# CAN_Interface.net
KiCad netlist of a schematic drawn in Altium Designer
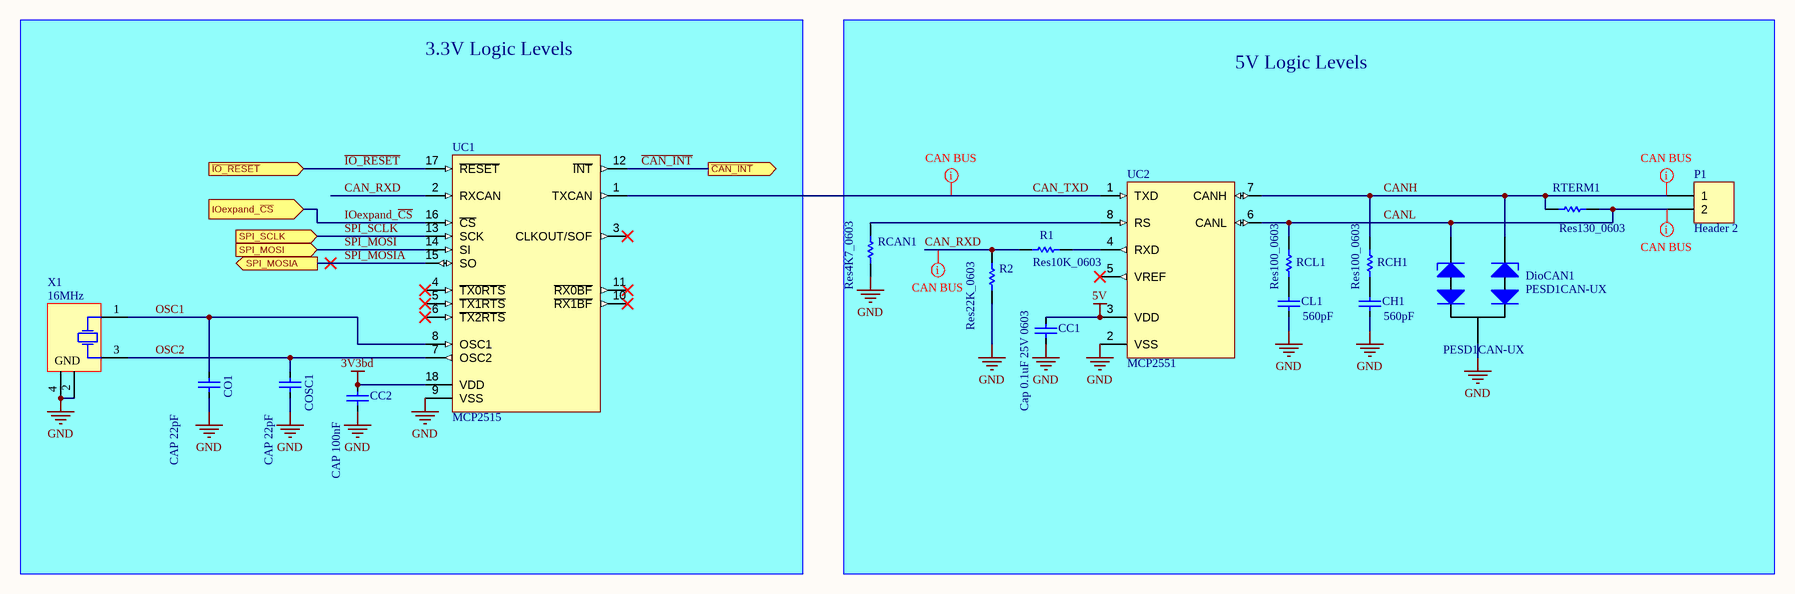
[diagram p0:  CAN_Interface.SchDoc]

(export (version "E")
  (design (tool "Eeschema 10.0.6"))
  (components
    (comp (ref "CC1")
      (value "Cap 0.1uF 25V 0603")
      (footprint "0603C_L")
      (description "Cap0.1uF_25V_0603")
      (libsource (lib "MHH -  Altium Advanced Course A365 01") (part "CMP-00001-1"))
    )
    (comp (ref "CC2")
      (value "CAP 100nF")
      (footprint "0603C_L")
      (fields
        (field (name "MANUFACTURER") "Yageo")
        (field (name "MANUFACTURER PART NUMBER") "CC0603ZRY5V9BB104")
      )
      (libsource (lib "MHH -  Altium Advanced Course A365 01") (part "CMP-00119-2"))
    )
    (comp (ref "CH1")
      (value "560pF")
      (footprint "0603C_L")
      (description "560pF 25V 0603")
      (libsource (lib "MHH -  Altium Advanced Course A365 01") (part "CAP Horizontal Pin50mil"))
    )
    (comp (ref "CL1")
      (value "560pF")
      (footprint "0603C_L")
      (description "560pF 25V 0603")
      (libsource (lib "MHH -  Altium Advanced Course A365 01") (part "CAP Horizontal Pin50mil"))
    )
    (comp (ref "CO1")
      (value "CAP 22pF")
      (footprint "0603C_L")
      (fields
        (field (name "TOLERANCE") "5%")
        (field (name "MANUFACTURER") "Murata")
        (field (name "MANUFACTURER PART NUMBER") "GRM1885C1H220JA01D")
      )
      (libsource (lib "MHH -  Altium Advanced Course A365 01") (part "CMP-00026-1"))
    )
    (comp (ref "COSC1")
      (value "CAP 22pF")
      (footprint "0603C_L")
      (fields
        (field (name "TOLERANCE") "5%")
        (field (name "MANUFACTURER") "Murata")
        (field (name "MANUFACTURER PART NUMBER") "GRM1885C1H220JA01D")
      )
      (libsource (lib "MHH -  Altium Advanced Course A365 01") (part "CMP-00026-1"))
    )
    (comp (ref "DioCAN1")
      (value "PESD1CAN-UX")
      (footprint "SOT323")
      (description "Trans Voltage Suppressor Diode, 150W, 24V V(RWM), Bidirectional, 2 Element, Silicon")
      (fields
        (field (name "MANUFACTURER") "Nexperia")
        (field (name "MANUFACTURER PART NUMBER") "PESD1CAN-UX")
        (field (name "SOURCE") "WCT.SchLib")
      )
      (libsource (lib "MHH -  Altium Advanced Course A365 01") (part "CMP-00244-2"))
    )
    (comp (ref "P1")
      (value "Header 2")
      (footprint "HDR1X2")
      (description "Header, 2-Pin")
      (fields (field (name "PUBLISHER") "Altium Limited") (field (name "SOURCE") "WCT.SchLib"))
      (libsource (lib "MHH -  Altium Advanced Course A365 01") (part "Header 2"))
    )
    (comp (ref "R1")
      (value "Res10K_0603")
      (footprint "0603_L")
      (fields
        (field (name "MANUFACTURER") "Panasonic")
        (field (name "MANUFACTURER PART NUMBER") "ERJ-3GEYJ102V")
        (field (name "TOLERANCE") "5%")
        (field (name "SOURCE") "WCT.SchLib")
      )
      (libsource (lib "MHH -  Altium Advanced Course A365 01") (part "CMP-00098-1"))
    )
    (comp (ref "R2")
      (value "Res22K_0603")
      (footprint "0603_L")
      (description "RES22K 0.5% 0603")
      (fields
        (field (name "MANUFACTURER") "Yageo")
        (field (name "MANUFACTURER PART NUMBER") "RT0603DRD0722KL")
        (field (name "SOURCE") "WCT.SchLib")
      )
      (libsource (lib "MHH -  Altium Advanced Course A365 01") (part "CMP-00098-1"))
    )
    (comp (ref "RCAN1")
      (value "Res4K7_0603")
      (footprint "0603_L")
      (fields
        (field (name "MANUFACTURER") "Yageo")
        (field (name "MANUFACTURER PART NUMBER") "RT0603DRD074K99L")
        (field (name "TOLERANCE") "0.5%")
        (field (name "SOURCE") "WCT.SchLib")
      )
      (libsource (lib "MHH -  Altium Advanced Course A365 01") (part "CMP-00016-1"))
    )
    (comp (ref "RCH1")
      (value "Res100_0603")
      (footprint "0603_L")
      (fields
        (field (name "MANUFACTURER") "Panasonic Electronic Components")
        (field (name "TOLERANCE") "5%")
        (field (name "SOURCE") "WCT.SchLib")
      )
      (libsource (lib "MHH -  Altium Advanced Course A365 01") (part "CMP-00096-1"))
    )
    (comp (ref "RCL1")
      (value "Res100_0603")
      (footprint "0603_L")
      (fields
        (field (name "MANUFACTURER") "Panasonic Electronic Components")
        (field (name "TOLERANCE") "5%")
        (field (name "SOURCE") "WCT.SchLib")
      )
      (libsource (lib "MHH -  Altium Advanced Course A365 01") (part "CMP-00096-1"))
    )
    (comp (ref "RTERM1")
      (value "Res130_0603")
      (footprint "0603_L")
      (fields
        (field (name "MANUFACTURER") "Panasonic Electronic Components")
        (field (name "TOLERANCE") "5%")
        (field (name "SOURCE") "WCT.SchLib")
      )
      (libsource (lib "MHH -  Altium Advanced Course A365 01") (part "CMP-00199-1"))
    )
    (comp (ref "UC1")
      (value "MCP2515")
      (footprint "SOIC-SO18_M")
      (description "Stand-Alone CAN Controller With SPI Interface, 18-Pin SOIC, Extended Temperature")
      (fields
        (field (name "MANUFACTURER") "Microchip")
        (field (name "MANUFACTURER PART NUMBER") "MCP2515-E/SO")
        (field (name "AVAILABLE PREVIEW IMAGES") "2D")
        (field (name "SOURCE") "WCT.SchLib")
      )
      (libsource (lib "MHH -  Altium Advanced Course A365 01") (part "MCP2515"))
    )
    (comp (ref "UC2")
      (value "MCP2551")
      (footprint "SOIC-SN8_N")
      (description "High-Speed CAN Transceiver, 8-Pin SOIC, Extended Temperature")
      (fields
        (field (name "MANUFACTURER") "Microchip")
        (field (name "MANUFACTURER PART NUMBER") "MCP2551-E/SN")
        (field (name "AVAILABLE PREVIEW IMAGES") "2D")
        (field (name "SOURCE") "WCT.SchLib")
      )
      (libsource (lib "MHH -  Altium Advanced Course A365 01") (part "MCP2551"))
    )
    (comp (ref "X1")
      (value "Crystal 4Pin")
      (footprint "FP-ABM8-MFG")
      (description "Crystal 16MHz ±20ppm 18pF SMD-4 3.2mm x 2.5mm CSTCE16M0V53-R0 ABM8-16.000MHZ-B2-T")
      (fields
        (field (name "TOLERANCE") "20ppm")
        (field (name "FREQUENCY") "16MHz")
        (field (name "MANUFACTURER") "Murata")
        (field (name "SOURCE") "WCT.SchLib")
      )
      (libsource (lib "MHH -  Altium Advanced Course A365 01") (part "Crystal 4Pin"))
    )
  )
  (nets
    (net (code "1") (name "/CANH") (class "Default")
      (node (ref "DioCAN1") (pin "1") (pinfunction "A_1") (pintype "passive"))
      (node (ref "P1") (pin "1") (pinfunction "1_1") (pintype "passive"))
      (node (ref "RCH1") (pin "2") (pinfunction "2_2") (pintype "passive"))
      (node (ref "RTERM1") (pin "2") (pinfunction "2_2") (pintype "passive"))
      (node (ref "UC2") (pin "7") (pinfunction "CANH_7") (pintype "bidirectional"))
    )
    (net (code "2") (name "/CANL") (class "Default")
      (node (ref "DioCAN1") (pin "2") (pinfunction "K_2") (pintype "passive"))
      (node (ref "P1") (pin "2") (pinfunction "2_2") (pintype "passive"))
      (node (ref "RCL1") (pin "2") (pinfunction "2_2") (pintype "passive"))
      (node (ref "RTERM1") (pin "1") (pinfunction "1_1") (pintype "passive"))
      (node (ref "UC2") (pin "6") (pinfunction "CANL_6") (pintype "bidirectional"))
    )
    (net (code "3") (name "/CAN_INT") (class "Default")
      (node (ref "UC1") (pin "12") (pinfunction "~{INT}_12") (pintype "output"))
    )
    (net (code "4") (name "/CAN_RXD") (class "Default")
      (node (ref "R1") (pin "2") (pinfunction "2_2") (pintype "passive"))
      (node (ref "R2") (pin "2") (pinfunction "2_2") (pintype "passive"))
      (node (ref "UC1") (pin "2") (pinfunction "RXCAN_2") (pintype "input"))
    )
    (net (code "5") (name "/CAN_TXD") (class "Default")
      (node (ref "UC1") (pin "1") (pinfunction "TXCAN_1") (pintype "output"))
      (node (ref "UC2") (pin "1") (pinfunction "TXD_1") (pintype "input"))
    )
    (net (code "6") (name "/IO_RESET") (class "Default")
      (node (ref "UC1") (pin "17") (pinfunction "~{RESET}_17") (pintype "input"))
    )
    (net (code "7") (name "/IOexpand_~{CS}") (class "Default")
      (node (ref "UC1") (pin "16") (pinfunction "~{CS}_16") (pintype "input"))
    )
    (net (code "8") (name "/OSC1") (class "Default")
      (node (ref "CO1") (pin "2") (pinfunction "2_2") (pintype "passive"))
      (node (ref "UC1") (pin "8") (pinfunction "OSC1_8") (pintype "input"))
      (node (ref "X1") (pin "1") (pinfunction "1_1") (pintype "passive"))
    )
    (net (code "9") (name "/OSC2") (class "Default")
      (node (ref "COSC1") (pin "2") (pinfunction "2_2") (pintype "passive"))
      (node (ref "UC1") (pin "7") (pinfunction "OSC2_7") (pintype "output"))
      (node (ref "X1") (pin "3") (pinfunction "3_3") (pintype "passive"))
    )
    (net (code "10") (name "/SPI_MOSI") (class "Default")
      (node (ref "UC1") (pin "14") (pinfunction "SI_14") (pintype "input"))
    )
    (net (code "11") (name "/SPI_MOSIA") (class "Default")
      (node (ref "UC1") (pin "15") (pinfunction "SO_15") (pintype "bidirectional"))
    )
    (net (code "12") (name "/SPI_SCLK") (class "Default")
      (node (ref "UC1") (pin "13") (pinfunction "SCK_13") (pintype "input"))
    )
    (net (code "13") (name "3V3bd") (class "Default")
      (node (ref "CC2") (pin "2") (pinfunction "2_2") (pintype "passive"))
      (node (ref "UC1") (pin "18") (pinfunction "VDD_18") (pintype "power_in"))
    )
    (net (code "14") (name "5V") (class "Default")
      (node (ref "CC1") (pin "2") (pinfunction "2_2") (pintype "passive"))
      (node (ref "UC2") (pin "3") (pinfunction "VDD_3") (pintype "power_in"))
    )
    (net (code "15") (name "GND") (class "Default")
      (node (ref "CC1") (pin "1") (pinfunction "1_1") (pintype "passive"))
      (node (ref "CC2") (pin "1") (pinfunction "1_1") (pintype "passive"))
      (node (ref "CH1") (pin "2") (pinfunction "2_2") (pintype "passive"))
      (node (ref "CL1") (pin "1") (pinfunction "1_1") (pintype "passive"))
      (node (ref "CO1") (pin "1") (pinfunction "1_1") (pintype "passive"))
      (node (ref "COSC1") (pin "1") (pinfunction "1_1") (pintype "passive"))
      (node (ref "DioCAN1") (pin "3") (pinfunction "3_3") (pintype "passive"))
      (node (ref "R2") (pin "1") (pinfunction "1_1") (pintype "passive"))
      (node (ref "RCAN1") (pin "1") (pinfunction "1_1") (pintype "passive"))
      (node (ref "UC1") (pin "9") (pinfunction "VSS_9") (pintype "power_in"))
      (node (ref "UC2") (pin "2") (pinfunction "VSS_2") (pintype "power_in"))
      (node (ref "X1") (pin "2") (pinfunction "GND_2") (pintype "power_in"))
      (node (ref "X1") (pin "4") (pinfunction "GND_4") (pintype "power_in"))
    )
    (net (code "16") (name "Net-(CH1-Pad1)") (class "Default")
      (node (ref "CH1") (pin "1") (pinfunction "1_1") (pintype "passive"))
      (node (ref "RCH1") (pin "1") (pinfunction "1_1") (pintype "passive"))
    )
    (net (code "17") (name "Net-(CL1-Pad2)") (class "Default")
      (node (ref "CL1") (pin "2") (pinfunction "2_2") (pintype "passive"))
      (node (ref "RCL1") (pin "1") (pinfunction "1_1") (pintype "passive"))
    )
    (net (code "18") (name "Net-(UC2-RS)") (class "Default")
      (node (ref "RCAN1") (pin "2") (pinfunction "2_2") (pintype "passive"))
      (node (ref "UC2") (pin "8") (pinfunction "RS_8") (pintype "input"))
    )
    (net (code "19") (name "Net-(UC2-RXD)") (class "Default")
      (node (ref "R1") (pin "1") (pinfunction "1_1") (pintype "passive"))
      (node (ref "UC2") (pin "4") (pinfunction "RXD_4") (pintype "output"))
    )
    (net (code "20") (name "unconnected-(UC1-CLKOUT{slash}SOF-Pad3)") (class "Default")
      (node (ref "UC1") (pin "3") (pinfunction "CLKOUT/SOF_3") (pintype "output+no_connect"))
    )
    (net (code "21") (name "unconnected-(UC1-~{RX0BF}-Pad11)") (class "Default")
      (node (ref "UC1") (pin "11") (pinfunction "~{RX0BF}_11") (pintype "output+no_connect"))
    )
    (net (code "22") (name "unconnected-(UC1-~{RX1BF}-Pad10)") (class "Default")
      (node (ref "UC1") (pin "10") (pinfunction "~{RX1BF}_10") (pintype "output+no_connect"))
    )
    (net (code "23") (name "unconnected-(UC1-~{TX0RTS}-Pad4)") (class "Default")
      (node (ref "UC1") (pin "4") (pinfunction "~{TX0RTS}_4") (pintype "input+no_connect"))
    )
    (net (code "24") (name "unconnected-(UC1-~{TX1RTS}-Pad5)") (class "Default")
      (node (ref "UC1") (pin "5") (pinfunction "~{TX1RTS}_5") (pintype "input+no_connect"))
    )
    (net (code "25") (name "unconnected-(UC1-~{TX2RTS}-Pad6)") (class "Default")
      (node (ref "UC1") (pin "6") (pinfunction "~{TX2RTS}_6") (pintype "input+no_connect"))
    )
    (net (code "26") (name "unconnected-(UC2-VREF-Pad5)") (class "Default")
      (node (ref "UC2") (pin "5") (pinfunction "VREF_5") (pintype "output+no_connect"))
    )
  )
)
